# MEMORIES.net
KiCad netlist of a schematic drawn in Altium Designer
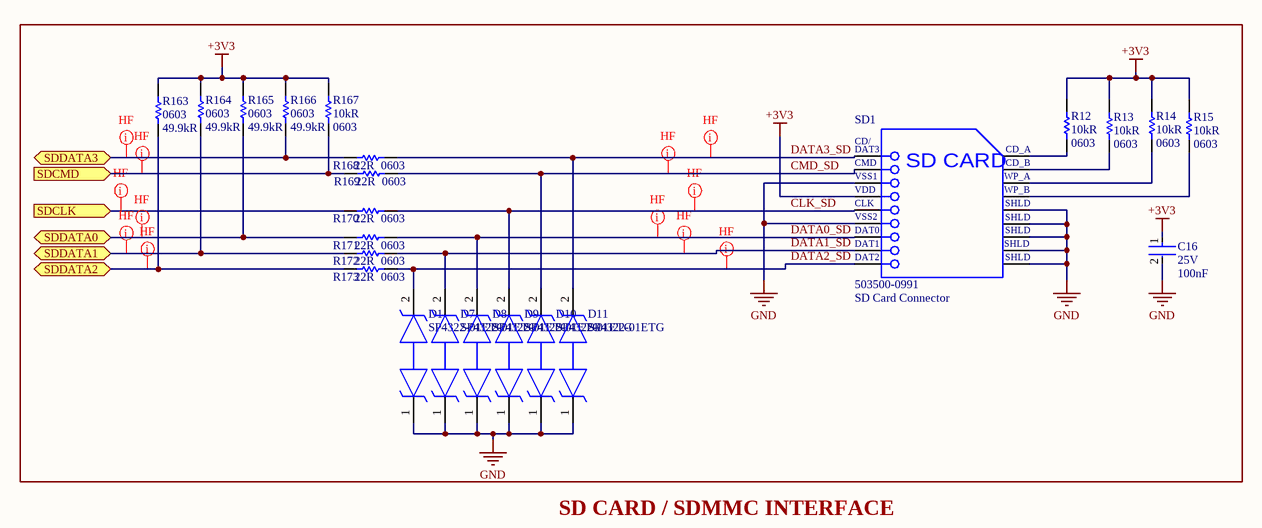
[diagram p0: MEMORIES.SchDoc]

(export (version "E")
  (design (tool "Eeschema 10.0.6"))
  (components
    (comp (ref "C16")
      (value "CGA3E2X7R1E104K080AA")
      (footprint "FP-CGA3E-0_3-0_1-MFG")
      (description "Cap Ceramic 100nF 25V X7R 10% Pad SMD 0603 +125°C Automotive T/R")
      (fields
        (field (name "VOLTAGE RATING (DC)") "25V")
        (field (name "CAPACITANCE") "100nF")
        (field (name "TOLERANCE") "10%")
        (field (name "MANUFACTURER") "TDK")
      )
      (libsource (lib "Altium Content Vault") (part "b4654b650e69147ec39a6b967a45e02"))
    )
    (comp (ref "D1")
      (value "SP4322-01ETG")
      (footprint "SamacSys:SP432201ETG")
      (description "TVS Diode (Bi-directional)")
      (fields (field (name "MOUSER PART NUMBER") "576-SP4322-01ETG"))
      (libsource (lib "*") (part "SP4322-01ETG"))
    )
    (comp (ref "D7")
      (value "SP4322-01ETG")
      (footprint "SamacSys:SP432201ETG")
      (description "TVS Diode (Bi-directional)")
      (fields (field (name "MOUSER PART NUMBER") "576-SP4322-01ETG"))
      (libsource (lib "*") (part "SP4322-01ETG"))
    )
    (comp (ref "D8")
      (value "SP4322-01ETG")
      (footprint "SamacSys:SP432201ETG")
      (description "TVS Diode (Bi-directional)")
      (fields (field (name "MOUSER PART NUMBER") "576-SP4322-01ETG"))
      (libsource (lib "*") (part "SP4322-01ETG"))
    )
    (comp (ref "D9")
      (value "SP4322-01ETG")
      (footprint "SamacSys:SP432201ETG")
      (description "TVS Diode (Bi-directional)")
      (fields (field (name "MOUSER PART NUMBER") "576-SP4322-01ETG"))
      (libsource (lib "*") (part "SP4322-01ETG"))
    )
    (comp (ref "D10")
      (value "SP4322-01ETG")
      (footprint "SamacSys:SP432201ETG")
      (description "TVS Diode (Bi-directional)")
      (fields (field (name "MOUSER PART NUMBER") "576-SP4322-01ETG"))
      (libsource (lib "*") (part "SP4322-01ETG"))
    )
    (comp (ref "D11")
      (value "SP4322-01ETG")
      (footprint "SamacSys:SP432201ETG")
      (description "TVS Diode (Bi-directional)")
      (fields (field (name "MOUSER PART NUMBER") "576-SP4322-01ETG"))
      (libsource (lib "*") (part "SP4322-01ETG"))
    )
    (comp (ref "R12")
      (value "ERJ3EKF1002V")
      (footprint "RESC1609X55X30LL15T15")
      (description "Chip Resistor, 10 KOhm, +/- 1%, 0.1 W, -55 to 155 degC, 0603 (1608 Metric), RoHS, Tape and Reel")
      (fields
        (field (name "RESISTANCE") "10kR")
        (field (name "CASE CODE (IMPERIAL)") "0603")
        (field (name "TOLERANCE") "1%")
        (field (name "MANUFACTURER") "Panasonic")
      )
      (libsource (lib "Altium Content Vault") (part "RES-2"))
    )
    (comp (ref "R13")
      (value "ERJ3EKF1002V")
      (footprint "RESC1609X55X30LL15T15")
      (description "Chip Resistor, 10 KOhm, +/- 1%, 0.1 W, -55 to 155 degC, 0603 (1608 Metric), RoHS, Tape and Reel")
      (fields
        (field (name "RESISTANCE") "10kR")
        (field (name "CASE CODE (IMPERIAL)") "0603")
        (field (name "TOLERANCE") "1%")
        (field (name "MANUFACTURER") "Panasonic")
      )
      (libsource (lib "Altium Content Vault") (part "RES-2"))
    )
    (comp (ref "R14")
      (value "ERJ3EKF1002V")
      (footprint "RESC1609X55X30LL15T15")
      (description "Chip Resistor, 10 KOhm, +/- 1%, 0.1 W, -55 to 155 degC, 0603 (1608 Metric), RoHS, Tape and Reel")
      (fields
        (field (name "RESISTANCE") "10kR")
        (field (name "CASE CODE (IMPERIAL)") "0603")
        (field (name "TOLERANCE") "1%")
        (field (name "MANUFACTURER") "Panasonic")
      )
      (libsource (lib "Altium Content Vault") (part "RES-2"))
    )
    (comp (ref "R15")
      (value "ERJ3EKF1002V")
      (footprint "RESC1609X55X30LL15T15")
      (description "Chip Resistor, 10 KOhm, +/- 1%, 0.1 W, -55 to 155 degC, 0603 (1608 Metric), RoHS, Tape and Reel")
      (fields
        (field (name "RESISTANCE") "10kR")
        (field (name "CASE CODE (IMPERIAL)") "0603")
        (field (name "TOLERANCE") "1%")
        (field (name "MANUFACTURER") "Panasonic")
      )
      (libsource (lib "Altium Content Vault") (part "RES-2"))
    )
    (comp (ref "R163")
      (value "ERJ-3EKF4992V")
      (footprint "RESC1608X55X30ML15T15")
      (fields
        (field (name "MANUFACTURER") "Panasonic")
        (field (name "CASE CODE (IMPERIAL)") "0603")
        (field (name "RESISTANCE") "49.9kR")
        (field (name "TOLERANCE") "1%")
      )
      (libsource (lib "Altium Content Vault") (part "RES"))
    )
    (comp (ref "R164")
      (value "ERJ-3EKF4992V")
      (footprint "RESC1608X55X30ML15T15")
      (fields
        (field (name "MANUFACTURER") "Panasonic")
        (field (name "CASE CODE (IMPERIAL)") "0603")
        (field (name "RESISTANCE") "49.9kR")
        (field (name "TOLERANCE") "1%")
      )
      (libsource (lib "Altium Content Vault") (part "RES"))
    )
    (comp (ref "R165")
      (value "ERJ-3EKF4992V")
      (footprint "RESC1608X55X30ML15T15")
      (fields
        (field (name "MANUFACTURER") "Panasonic")
        (field (name "CASE CODE (IMPERIAL)") "0603")
        (field (name "RESISTANCE") "49.9kR")
        (field (name "TOLERANCE") "1%")
      )
      (libsource (lib "Altium Content Vault") (part "RES"))
    )
    (comp (ref "R166")
      (value "ERJ-3EKF4992V")
      (footprint "RESC1608X55X30ML15T15")
      (fields
        (field (name "MANUFACTURER") "Panasonic")
        (field (name "CASE CODE (IMPERIAL)") "0603")
        (field (name "RESISTANCE") "49.9kR")
        (field (name "TOLERANCE") "1%")
      )
      (libsource (lib "Altium Content Vault") (part "RES"))
    )
    (comp (ref "R167")
      (value "ERJ3EKF1002V")
      (footprint "RESC1609X55X30LL15T15")
      (description "Chip Resistor, 10 KOhm, +/- 1%, 0.1 W, -55 to 155 degC, 0603 (1608 Metric), RoHS, Tape and Reel")
      (fields
        (field (name "RESISTANCE") "10kR")
        (field (name "CASE CODE (IMPERIAL)") "0603")
        (field (name "TOLERANCE") "1%")
        (field (name "MANUFACTURER") "Panasonic")
      )
      (libsource (lib "Altium Content Vault") (part "RES-2"))
    )
    (comp (ref "R168")
      (value "ERJ-3EKF22R0V")
      (footprint "RESC1608X55X30LL15T15")
      (description "Chip Resistor, 22 Ohm, +/- 1%, 0.1 W, -55 to 155 degC, 0603 (1608 Metric), RoHS, Tape and Reel")
      (fields
        (field (name "MANUFACTURER") "Panasonic")
        (field (name "MANUFACTURER PART NUMBER") "ERJ3EKF22R0V")
        (field (name "CASE CODE (IMPERIAL)") "0603")
        (field (name "RESISTANCE") "22R")
      )
      (libsource (lib "Altium Content Vault") (part "RES-2"))
    )
    (comp (ref "R169")
      (value "ERJ-3EKF22R0V")
      (footprint "RESC1608X55X30LL15T15")
      (description "Chip Resistor, 22 Ohm, +/- 1%, 0.1 W, -55 to 155 degC, 0603 (1608 Metric), RoHS, Tape and Reel")
      (fields
        (field (name "MANUFACTURER") "Panasonic")
        (field (name "MANUFACTURER PART NUMBER") "ERJ3EKF22R0V")
        (field (name "CASE CODE (IMPERIAL)") "0603")
        (field (name "RESISTANCE") "22R")
      )
      (libsource (lib "Altium Content Vault") (part "RES-2"))
    )
    (comp (ref "R170")
      (value "ERJ-3EKF22R0V")
      (footprint "RESC1608X55X30LL15T15")
      (description "Chip Resistor, 22 Ohm, +/- 1%, 0.1 W, -55 to 155 degC, 0603 (1608 Metric), RoHS, Tape and Reel")
      (fields
        (field (name "MANUFACTURER") "Panasonic")
        (field (name "MANUFACTURER PART NUMBER") "ERJ3EKF22R0V")
        (field (name "CASE CODE (IMPERIAL)") "0603")
        (field (name "RESISTANCE") "22R")
      )
      (libsource (lib "Altium Content Vault") (part "RES-2"))
    )
    (comp (ref "R171")
      (value "ERJ-3EKF22R0V")
      (footprint "RESC1608X55X30LL15T15")
      (description "Chip Resistor, 22 Ohm, +/- 1%, 0.1 W, -55 to 155 degC, 0603 (1608 Metric), RoHS, Tape and Reel")
      (fields
        (field (name "MANUFACTURER") "Panasonic")
        (field (name "MANUFACTURER PART NUMBER") "ERJ3EKF22R0V")
        (field (name "CASE CODE (IMPERIAL)") "0603")
        (field (name "RESISTANCE") "22R")
      )
      (libsource (lib "Altium Content Vault") (part "RES-2"))
    )
    (comp (ref "R172")
      (value "ERJ-3EKF22R0V")
      (footprint "RESC1608X55X30LL15T15")
      (description "Chip Resistor, 22 Ohm, +/- 1%, 0.1 W, -55 to 155 degC, 0603 (1608 Metric), RoHS, Tape and Reel")
      (fields
        (field (name "MANUFACTURER") "Panasonic")
        (field (name "MANUFACTURER PART NUMBER") "ERJ3EKF22R0V")
        (field (name "CASE CODE (IMPERIAL)") "0603")
        (field (name "RESISTANCE") "22R")
      )
      (libsource (lib "Altium Content Vault") (part "RES-2"))
    )
    (comp (ref "R173")
      (value "ERJ-3EKF22R0V")
      (footprint "RESC1608X55X30LL15T15")
      (description "Chip Resistor, 22 Ohm, +/- 1%, 0.1 W, -55 to 155 degC, 0603 (1608 Metric), RoHS, Tape and Reel")
      (fields
        (field (name "MANUFACTURER") "Panasonic")
        (field (name "MANUFACTURER PART NUMBER") "ERJ3EKF22R0V")
        (field (name "CASE CODE (IMPERIAL)") "0603")
        (field (name "RESISTANCE") "22R")
      )
      (libsource (lib "Altium Content Vault") (part "RES-2"))
    )
    (comp (ref "SD1")
      (value "503500-0991")
      (footprint "MOLX-503500-0991_V")
      (description "SD and Combo Memory Card Connector, 9 Position Surface Mount, -25 to 85 degC, RoHS, Tape and Reel")
      (fields (field (name "PACKAGEDESCRIPTION") "SD Card Connector") (field (name "MANUFACTURER") "Molex"))
      (libsource (lib "Altium Content Vault") (part "CN-SD-9-4SW-5S"))
    )
  )
  (nets
    (net (code "1") (name "+3V3") (class "Default")
      (node (ref "C16") (pin "1") (pinfunction "1_1") (pintype "passive"))
      (node (ref "R12") (pin "2") (pinfunction "2_2") (pintype "passive"))
      (node (ref "R13") (pin "2") (pinfunction "2_2") (pintype "passive"))
      (node (ref "R14") (pin "2") (pinfunction "2_2") (pintype "passive"))
      (node (ref "R15") (pin "2") (pinfunction "2_2") (pintype "passive"))
      (node (ref "R163") (pin "2") (pinfunction "2_2") (pintype "passive"))
      (node (ref "R164") (pin "2") (pinfunction "2_2") (pintype "passive"))
      (node (ref "R165") (pin "2") (pinfunction "2_2") (pintype "passive"))
      (node (ref "R166") (pin "2") (pinfunction "2_2") (pintype "passive"))
      (node (ref "R167") (pin "2") (pinfunction "2_2") (pintype "passive"))
      (node (ref "SD1") (pin "4") (pinfunction "VDD_4") (pintype "passive"))
    )
    (net (code "2") (name "/CLK_SD") (class "Default")
      (node (ref "D9") (pin "2") (pinfunction "2_2") (pintype "passive"))
      (node (ref "R170") (pin "2") (pinfunction "2_2") (pintype "passive"))
      (node (ref "SD1") (pin "5") (pinfunction "CLK_5") (pintype "passive"))
    )
    (net (code "3") (name "/CMD_SD") (class "Default")
      (node (ref "D10") (pin "2") (pinfunction "2_2") (pintype "passive"))
      (node (ref "R169") (pin "2") (pinfunction "2_2") (pintype "passive"))
      (node (ref "SD1") (pin "2") (pinfunction "CMD_2") (pintype "passive"))
    )
    (net (code "4") (name "/DATA0_SD") (class "Default")
      (node (ref "D8") (pin "2") (pinfunction "2_2") (pintype "passive"))
      (node (ref "R171") (pin "2") (pinfunction "2_2") (pintype "passive"))
      (node (ref "SD1") (pin "7") (pinfunction "DAT0_7") (pintype "passive"))
    )
    (net (code "5") (name "/DATA1_SD") (class "Default")
      (node (ref "D7") (pin "2") (pinfunction "2_2") (pintype "passive"))
      (node (ref "R172") (pin "2") (pinfunction "2_2") (pintype "passive"))
      (node (ref "SD1") (pin "8") (pinfunction "DAT1_8") (pintype "passive"))
    )
    (net (code "6") (name "/DATA2_SD") (class "Default")
      (node (ref "D1") (pin "2") (pinfunction "2_2") (pintype "passive"))
      (node (ref "R173") (pin "2") (pinfunction "2_2") (pintype "passive"))
      (node (ref "SD1") (pin "9") (pinfunction "DAT2_9") (pintype "passive"))
    )
    (net (code "7") (name "/DATA3_SD") (class "Default")
      (node (ref "D11") (pin "2") (pinfunction "2_2") (pintype "passive"))
      (node (ref "R168") (pin "2") (pinfunction "2_2") (pintype "passive"))
      (node (ref "SD1") (pin "1") (pinfunction "CD/DAT3_1") (pintype "passive"))
    )
    (net (code "8") (name "/SDCLK") (class "Default")
      (node (ref "R170") (pin "1") (pinfunction "1_1") (pintype "passive"))
    )
    (net (code "9") (name "/SDCMD") (class "Default")
      (node (ref "R167") (pin "1") (pinfunction "1_1") (pintype "passive"))
      (node (ref "R169") (pin "1") (pinfunction "1_1") (pintype "passive"))
    )
    (net (code "10") (name "/SDDATA0") (class "Default")
      (node (ref "R165") (pin "1") (pinfunction "1_1") (pintype "passive"))
      (node (ref "R171") (pin "1") (pinfunction "1_1") (pintype "passive"))
    )
    (net (code "11") (name "/SDDATA1") (class "Default")
      (node (ref "R164") (pin "1") (pinfunction "1_1") (pintype "passive"))
      (node (ref "R172") (pin "1") (pinfunction "1_1") (pintype "passive"))
    )
    (net (code "12") (name "/SDDATA2") (class "Default")
      (node (ref "R163") (pin "1") (pinfunction "1_1") (pintype "passive"))
      (node (ref "R173") (pin "1") (pinfunction "1_1") (pintype "passive"))
    )
    (net (code "13") (name "/SDDATA3") (class "Default")
      (node (ref "R166") (pin "1") (pinfunction "1_1") (pintype "passive"))
      (node (ref "R168") (pin "1") (pinfunction "1_1") (pintype "passive"))
    )
    (net (code "14") (name "GND") (class "Default")
      (node (ref "C16") (pin "2") (pinfunction "2_2") (pintype "passive"))
      (node (ref "D1") (pin "1") (pinfunction "1_1") (pintype "passive"))
      (node (ref "D10") (pin "1") (pinfunction "1_1") (pintype "passive"))
      (node (ref "D11") (pin "1") (pinfunction "1_1") (pintype "passive"))
      (node (ref "D7") (pin "1") (pinfunction "1_1") (pintype "passive"))
      (node (ref "D8") (pin "1") (pinfunction "1_1") (pintype "passive"))
      (node (ref "D9") (pin "1") (pinfunction "1_1") (pintype "passive"))
      (node (ref "SD1") (pin "14") (pinfunction "SHLD1_14") (pintype "passive"))
      (node (ref "SD1") (pin "15") (pinfunction "SHLD2_15") (pintype "passive"))
      (node (ref "SD1") (pin "16") (pinfunction "SHLD3_16") (pintype "passive"))
      (node (ref "SD1") (pin "17") (pinfunction "SHLD4_17") (pintype "passive"))
      (node (ref "SD1") (pin "18") (pinfunction "SHLD5_18") (pintype "passive"))
      (node (ref "SD1") (pin "3") (pinfunction "VSS1_3") (pintype "passive"))
      (node (ref "SD1") (pin "6") (pinfunction "VSS2_6") (pintype "passive"))
    )
    (net (code "15") (name "Net-(SD1-CD_A)") (class "Default")
      (node (ref "R12") (pin "1") (pinfunction "1_1") (pintype "passive"))
      (node (ref "SD1") (pin "10") (pinfunction "CD_A_10") (pintype "passive"))
    )
    (net (code "16") (name "Net-(SD1-CD_B)") (class "Default")
      (node (ref "R13") (pin "1") (pinfunction "1_1") (pintype "passive"))
      (node (ref "SD1") (pin "11") (pinfunction "CD_B_11") (pintype "passive"))
    )
    (net (code "17") (name "Net-(SD1-WP_A)") (class "Default")
      (node (ref "R14") (pin "1") (pinfunction "1_1") (pintype "passive"))
      (node (ref "SD1") (pin "12") (pinfunction "WP_A_12") (pintype "passive"))
    )
    (net (code "18") (name "Net-(SD1-WP_B)") (class "Default")
      (node (ref "R15") (pin "1") (pinfunction "1_1") (pintype "passive"))
      (node (ref "SD1") (pin "13") (pinfunction "WP_B_13") (pintype "passive"))
    )
  )
)
